# Adafruit_Feather_ESP32-S2_Reverse_TFT.net
KiCad netlist of a schematic drawn in EAGLE
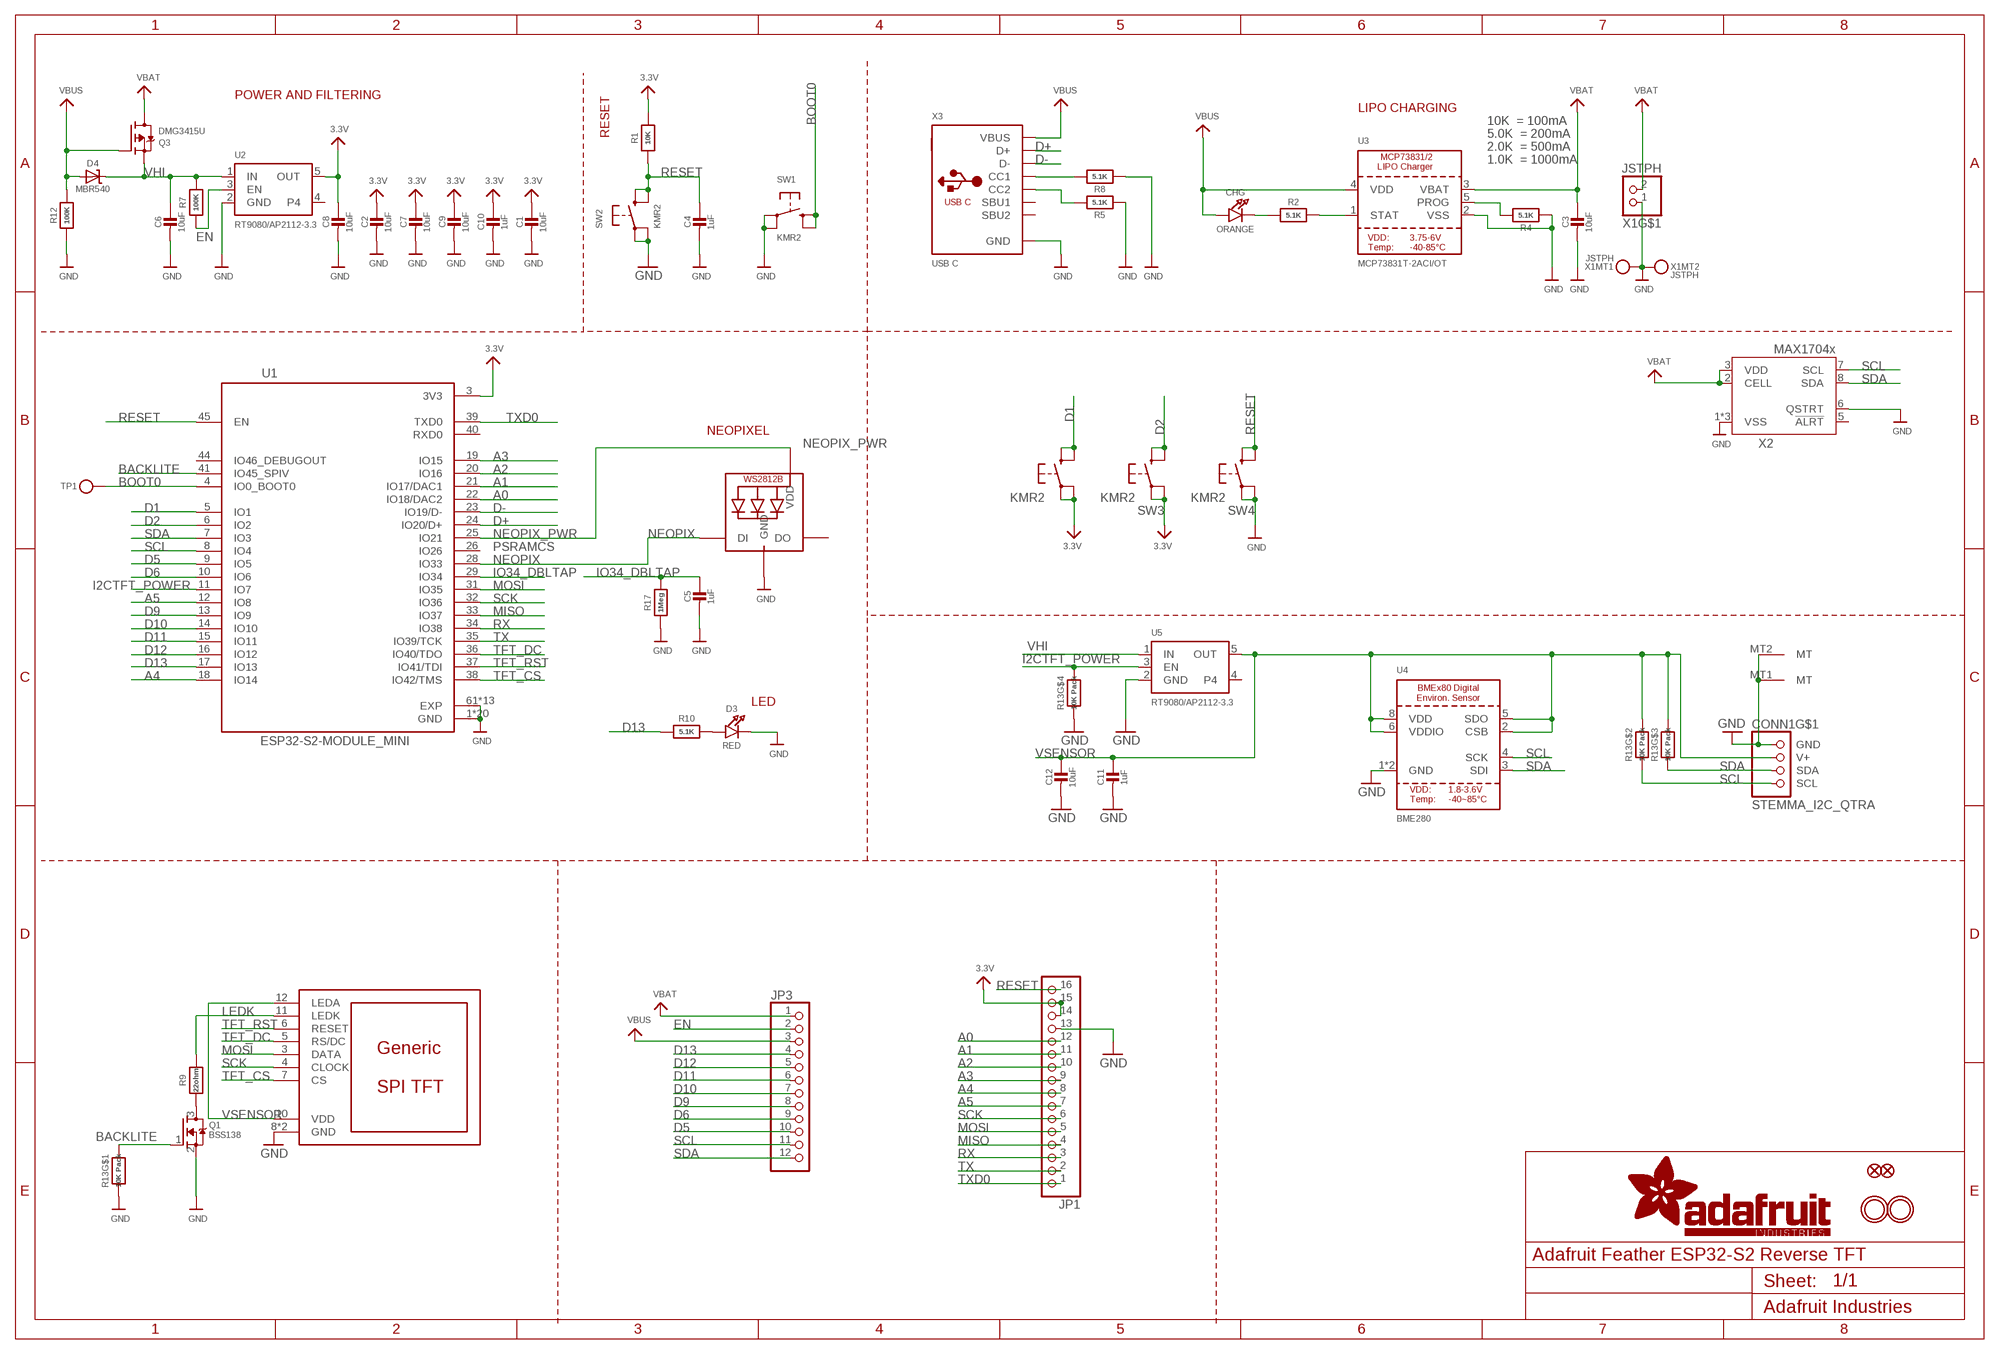
[diagram p0: schematic, sheet 1]

(export (version "E")
  (design (tool "Eeschema 10.0.6"))
  (components
    (comp (ref "C1")
      (value "10uF")
      (footprint "eagle-import:0805-NO")
      (libsource (lib "eagle-import") (part "CAP_CERAMIC0805-NOOUTLINE"))
    )
    (comp (ref "C2")
      (value "10uF")
      (footprint "eagle-import:0805-NO")
      (libsource (lib "eagle-import") (part "CAP_CERAMIC0805-NOOUTLINE"))
    )
    (comp (ref "C3")
      (value "10uF")
      (footprint "eagle-import:0805-NO")
      (libsource (lib "eagle-import") (part "CAP_CERAMIC0805-NOOUTLINE"))
    )
    (comp (ref "C4")
      (value "1uF")
      (footprint "eagle-import:0603-NO")
      (libsource (lib "eagle-import") (part "CAP_CERAMIC0603_NO"))
    )
    (comp (ref "C5")
      (value "1uF")
      (footprint "eagle-import:0603-NO")
      (libsource (lib "eagle-import") (part "CAP_CERAMIC0603_NO"))
    )
    (comp (ref "C6")
      (value "10uF")
      (footprint "eagle-import:0805-NO")
      (libsource (lib "eagle-import") (part "CAP_CERAMIC0805-NOOUTLINE"))
    )
    (comp (ref "C7")
      (value "10uF")
      (footprint "eagle-import:0805-NO")
      (libsource (lib "eagle-import") (part "CAP_CERAMIC0805-NOOUTLINE"))
    )
    (comp (ref "C8")
      (value "10uF")
      (footprint "eagle-import:0805-NO")
      (libsource (lib "eagle-import") (part "CAP_CERAMIC0805-NOOUTLINE"))
    )
    (comp (ref "C9")
      (value "10uF")
      (footprint "eagle-import:0805-NO")
      (libsource (lib "eagle-import") (part "CAP_CERAMIC0805-NOOUTLINE"))
    )
    (comp (ref "C10")
      (value "1uF")
      (footprint "eagle-import:0603-NO")
      (libsource (lib "eagle-import") (part "CAP_CERAMIC0603_NO"))
    )
    (comp (ref "C11")
      (value "1uF")
      (footprint "eagle-import:0603-NO")
      (libsource (lib "eagle-import") (part "CAP_CERAMIC0603_NO"))
    )
    (comp (ref "C12")
      (value "10uF")
      (footprint "eagle-import:0805-NO")
      (libsource (lib "eagle-import") (part "CAP_CERAMIC0805-NOOUTLINE"))
    )
    (comp (ref "CHG")
      (value "ORANGE")
      (footprint "eagle-import:CHIPLED_0603_NOOUTLINE")
      (libsource (lib "eagle-import") (part "LED0603_NOOUTLINE"))
    )
    (comp (ref "CONN1")
      (value "STEMMA_I2C_QTRA")
      (footprint "eagle-import:JST_SH4_RA")
      (libsource (lib "eagle-import") (part "STEMMA_I2C_QTRA"))
    )
    (comp (ref "D3")
      (value "RED")
      (footprint "eagle-import:CHIPLED_0603_NOOUTLINE")
      (libsource (lib "eagle-import") (part "LED0603_NOOUTLINE"))
    )
    (comp (ref "D4")
      (value "MBR540")
      (footprint "eagle-import:SOD-123")
      (libsource (lib "eagle-import") (part "DIODE-SCHOTTKYSOD-123"))
    )
    (comp (ref "DISP1")
      (value "DISP_LCD_GENERIC_SPI_1.14IN_240X135_WRAPUNDER")
      (footprint "eagle-import:TFT_1.14IN_240X135_WRAPUNDER")
      (libsource (lib "eagle-import") (part "DISP_LCD_GENERIC_SPI_1.14IN_240X135_WRAPUNDER"))
    )
    (comp (ref "JP1")
      (value "HEADER-1X16_MIN")
      (footprint "eagle-import:1X16_ROUND_MIN")
      (libsource (lib "eagle-import") (part "HEADER-1X16_MIN"))
    )
    (comp (ref "JP3")
      (value "HEADER-1X12_MIN")
      (footprint "eagle-import:1X12_ROUND_MIN")
      (libsource (lib "eagle-import") (part "HEADER-1X12_MIN"))
    )
    (comp (ref "LED1")
      (value "WS2812B_SK6805_1515")
      (footprint "eagle-import:SK6805_1515")
      (libsource (lib "eagle-import") (part "WS2812B_SK6805_1515"))
    )
    (comp (ref "Q1")
      (value "BSS138")
      (footprint "eagle-import:SC70")
      (libsource (lib "eagle-import") (part "MOSFET-N_SC70"))
    )
    (comp (ref "Q3")
      (value "DMG3415U")
      (footprint "eagle-import:SOT23-R")
      (libsource (lib "eagle-import") (part "MOSFET-P"))
    )
    (comp (ref "R1")
      (value "10K")
      (footprint "eagle-import:0603-NO")
      (libsource (lib "eagle-import") (part "RESISTOR_0603_NOOUT"))
    )
    (comp (ref "R2")
      (value "5.1K")
      (footprint "eagle-import:0603-NO")
      (libsource (lib "eagle-import") (part "RESISTOR_0603_NOOUT"))
    )
    (comp (ref "R4")
      (value "5.1K")
      (footprint "eagle-import:0603-NO")
      (libsource (lib "eagle-import") (part "RESISTOR_0603_NOOUT"))
    )
    (comp (ref "R5")
      (value "5.1K")
      (footprint "eagle-import:0603-NO")
      (libsource (lib "eagle-import") (part "RESISTOR_0603_NOOUT"))
    )
    (comp (ref "R7")
      (value "100K")
      (footprint "eagle-import:0603-NO")
      (libsource (lib "eagle-import") (part "RESISTOR_0603_NOOUT"))
    )
    (comp (ref "R8")
      (value "5.1K")
      (footprint "eagle-import:0603-NO")
      (libsource (lib "eagle-import") (part "RESISTOR_0603_NOOUT"))
    )
    (comp (ref "R9")
      (value "22ohm")
      (footprint "eagle-import:0603-NO")
      (libsource (lib "eagle-import") (part "RESISTOR_0603_NOOUT"))
    )
    (comp (ref "R10")
      (value "5.1K")
      (footprint "eagle-import:0603-NO")
      (libsource (lib "eagle-import") (part "RESISTOR_0603_NOOUT"))
    )
    (comp (ref "R12")
      (value "100K")
      (footprint "eagle-import:0603-NO")
      (libsource (lib "eagle-import") (part "RESISTOR_0603_NOOUT"))
    )
    (comp (ref "R13")
      (value "10K Pack")
      (footprint "eagle-import:RESPACK_4X0603")
      (libsource (lib "eagle-import") (part "RESISTOR_4PACK"))
    )
    (comp (ref "R17")
      (value "1Meg")
      (footprint "eagle-import:0603-NO")
      (libsource (lib "eagle-import") (part "RESISTOR_0603_NOOUT"))
    )
    (comp (ref "SW1")
      (value "KMR2")
      (footprint "eagle-import:BTN_RKB2_4.6X2.8")
      (libsource (lib "eagle-import") (part "SWITCH_TACT_SMT_RKB2"))
    )
    (comp (ref "SW2")
      (value "KMR2")
      (footprint "eagle-import:BTN_RKB2_4.6X2.8")
      (libsource (lib "eagle-import") (part "SWITCH_TACT_SMT_RKB2"))
    )
    (comp (ref "SW3")
      (value "KMR2")
      (footprint "eagle-import:BTN_RKB2_4.6X2.8")
      (libsource (lib "eagle-import") (part "SWITCH_TACT_SMT_RKB2"))
    )
    (comp (ref "SW4")
      (value "KMR2")
      (footprint "eagle-import:BTN_RKB2_4.6X2.8")
      (libsource (lib "eagle-import") (part "SWITCH_TACT_SMT_RKB2"))
    )
    (comp (ref "SW5")
      (value "KMR2")
      (footprint "eagle-import:BTN_RKB2_4.6X2.8")
      (libsource (lib "eagle-import") (part "SWITCH_TACT_SMT_RKB2"))
    )
    (comp (ref "TP1")
      (value "TESTPOINTROUND1.5MMNO")
      (footprint "eagle-import:TESTPOINT_ROUND_1.5MM_NO")
      (libsource (lib "eagle-import") (part "TESTPOINTROUND1.5MMNO"))
    )
    (comp (ref "U$31")
      (value "MOUNTINGHOLE2.5")
      (footprint "eagle-import:MOUNTINGHOLE_2.5_PLATED")
      (libsource (lib "eagle-import") (part "MOUNTINGHOLE2.5"))
    )
    (comp (ref "U$32")
      (value "MOUNTINGHOLE2.5")
      (footprint "eagle-import:MOUNTINGHOLE_2.5_PLATED")
      (libsource (lib "eagle-import") (part "MOUNTINGHOLE2.5"))
    )
    (comp (ref "U$34")
      (value "FIDUCIAL_1MM")
      (footprint "eagle-import:FIDUCIAL_1MM")
      (libsource (lib "eagle-import") (part "FIDUCIAL_1MM"))
    )
    (comp (ref "U$35")
      (value "FIDUCIAL_1MM")
      (footprint "eagle-import:FIDUCIAL_1MM")
      (libsource (lib "eagle-import") (part "FIDUCIAL_1MM"))
    )
    (comp (ref "U1")
      (value "ESP32-S2-MODULE_MINI")
      (footprint "eagle-import:ESP32-S2-MINI-1")
      (libsource (lib "eagle-import") (part "ESP32-S2-MODULE_MINI"))
    )
    (comp (ref "U2")
      (value "RT9080/AP2112-3.3")
      (footprint "eagle-import:SOT23-5")
      (fields (field (name "JLC_ROTATION") "0"))
      (libsource (lib "eagle-import") (part "VREG_SOT23-5"))
    )
    (comp (ref "U3")
      (value "MCP73831T-2ACI/OT")
      (footprint "eagle-import:SOT23-5")
      (libsource (lib "eagle-import") (part "MCP73831/2"))
    )
    (comp (ref "U4")
      (value "BME280")
      (footprint "eagle-import:BME280")
      (libsource (lib "eagle-import") (part "BME280"))
    )
    (comp (ref "U5")
      (value "RT9080/AP2112-3.3")
      (footprint "eagle-import:SOT23-5")
      (fields (field (name "JLC_ROTATION") "0"))
      (libsource (lib "eagle-import") (part "VREG_SOT23-5"))
    )
    (comp (ref "X1")
      (value "JSTPH")
      (footprint "eagle-import:JSTPH2_BATT")
      (libsource (lib "eagle-import") (part "CON_JST_PH_2PIN_MT_BATT"))
    )
    (comp (ref "X2")
      (value "MAX17048/T")
      (footprint "eagle-import:TDFN8_2X2MM")
      (libsource (lib "eagle-import") (part "MAX17048/T"))
    )
    (comp (ref "X3")
      (value "USB C")
      (footprint "eagle-import:USB_C_CUSB31-CFM2AX-01-X")
      (libsource (lib "eagle-import") (part "USB_C"))
    )
  )
  (nets
    (net (code "1") (name "/A0") (class "Default")
      (node (ref "JP1") (pin "12") (pinfunction "12_12") (pintype "passive"))
      (node (ref "U1") (pin "22") (pinfunction "IO18/DAC2_22") (pintype "bidirectional"))
    )
    (net (code "2") (name "/A1") (class "Default")
      (node (ref "JP1") (pin "11") (pinfunction "11_11") (pintype "passive"))
      (node (ref "U1") (pin "21") (pinfunction "IO17/DAC1_21") (pintype "bidirectional"))
    )
    (net (code "3") (name "/A2") (class "Default")
      (node (ref "JP1") (pin "10") (pinfunction "10_10") (pintype "passive"))
      (node (ref "U1") (pin "20") (pinfunction "IO16_20") (pintype "bidirectional"))
    )
    (net (code "4") (name "/A3") (class "Default")
      (node (ref "JP1") (pin "9") (pinfunction "9_9") (pintype "passive"))
      (node (ref "U1") (pin "19") (pinfunction "IO15_19") (pintype "bidirectional"))
    )
    (net (code "5") (name "/A4") (class "Default")
      (node (ref "JP1") (pin "8") (pinfunction "8_8") (pintype "passive"))
      (node (ref "U1") (pin "18") (pinfunction "IO14_18") (pintype "bidirectional"))
    )
    (net (code "6") (name "/A5") (class "Default")
      (node (ref "JP1") (pin "7") (pinfunction "7_7") (pintype "passive"))
      (node (ref "U1") (pin "12") (pinfunction "IO8_12") (pintype "bidirectional"))
    )
    (net (code "7") (name "/BACKLITE") (class "Default")
      (node (ref "Q1") (pin "1") (pinfunction "G_1") (pintype "bidirectional"))
      (node (ref "R13") (pin "8") (pinfunction "2_8") (pintype "passive"))
      (node (ref "U1") (pin "41") (pinfunction "IO45_SPIV_41") (pintype "bidirectional"))
    )
    (net (code "8") (name "/BOOT0") (class "Default")
      (node (ref "SW1") (pin "B") (pinfunction "S_B") (pintype "passive"))
      (node (ref "SW1") (pin "B'") (pinfunction "S1_B'") (pintype "passive"))
      (node (ref "TP1") (pin "P$1") (pinfunction "P$1_P$1") (pintype "bidirectional"))
      (node (ref "U1") (pin "4") (pinfunction "IO0_BOOT0_4") (pintype "bidirectional"))
    )
    (net (code "9") (name "/D+") (class "Default")
      (node (ref "U1") (pin "24") (pinfunction "IO20/D+_24") (pintype "bidirectional"))
      (node (ref "X3") (pin "A6") (pinfunction "D+_A6") (pintype "bidirectional"))
      (node (ref "X3") (pin "B6") (pinfunction "D+_B6") (pintype "bidirectional"))
    )
    (net (code "10") (name "/D-") (class "Default")
      (node (ref "U1") (pin "23") (pinfunction "IO19/D-_23") (pintype "bidirectional"))
      (node (ref "X3") (pin "A7") (pinfunction "D-_A7") (pintype "bidirectional"))
      (node (ref "X3") (pin "B7") (pinfunction "D-_B7") (pintype "bidirectional"))
    )
    (net (code "11") (name "/D1") (class "Default")
      (node (ref "SW5") (pin "B") (pinfunction "S_B") (pintype "passive"))
      (node (ref "SW5") (pin "B'") (pinfunction "S1_B'") (pintype "passive"))
      (node (ref "U1") (pin "5") (pinfunction "IO1_5") (pintype "bidirectional"))
    )
    (net (code "12") (name "/D2") (class "Default")
      (node (ref "SW3") (pin "B") (pinfunction "S_B") (pintype "passive"))
      (node (ref "SW3") (pin "B'") (pinfunction "S1_B'") (pintype "passive"))
      (node (ref "U1") (pin "6") (pinfunction "IO2_6") (pintype "bidirectional"))
    )
    (net (code "13") (name "/D5") (class "Default")
      (node (ref "JP3") (pin "10") (pinfunction "10_10") (pintype "passive"))
      (node (ref "U1") (pin "9") (pinfunction "IO5_9") (pintype "bidirectional"))
    )
    (net (code "14") (name "/D6") (class "Default")
      (node (ref "JP3") (pin "9") (pinfunction "9_9") (pintype "passive"))
      (node (ref "U1") (pin "10") (pinfunction "IO6_10") (pintype "bidirectional"))
    )
    (net (code "15") (name "/D9") (class "Default")
      (node (ref "JP3") (pin "8") (pinfunction "8_8") (pintype "passive"))
      (node (ref "U1") (pin "13") (pinfunction "IO9_13") (pintype "bidirectional"))
    )
    (net (code "16") (name "/D10") (class "Default")
      (node (ref "JP3") (pin "7") (pinfunction "7_7") (pintype "passive"))
      (node (ref "U1") (pin "14") (pinfunction "IO10_14") (pintype "bidirectional"))
    )
    (net (code "17") (name "/D11") (class "Default")
      (node (ref "JP3") (pin "6") (pinfunction "6_6") (pintype "passive"))
      (node (ref "U1") (pin "15") (pinfunction "IO11_15") (pintype "bidirectional"))
    )
    (net (code "18") (name "/D12") (class "Default")
      (node (ref "JP3") (pin "5") (pinfunction "5_5") (pintype "passive"))
      (node (ref "U1") (pin "16") (pinfunction "IO12_16") (pintype "bidirectional"))
    )
    (net (code "19") (name "/D13") (class "Default")
      (node (ref "JP3") (pin "4") (pinfunction "4_4") (pintype "passive"))
      (node (ref "R10") (pin "1") (pinfunction "1_1") (pintype "passive"))
      (node (ref "U1") (pin "17") (pinfunction "IO13_17") (pintype "bidirectional"))
    )
    (net (code "20") (name "/EN") (class "Default")
      (node (ref "JP3") (pin "2") (pinfunction "2_2") (pintype "passive"))
      (node (ref "R7") (pin "1") (pinfunction "1_1") (pintype "passive"))
      (node (ref "U2") (pin "3") (pinfunction "EN_3") (pintype "input"))
    )
    (net (code "21") (name "/I2CTFT_POWER") (class "Default")
      (node (ref "R13") (pin "5") (pinfunction "2_5") (pintype "passive"))
      (node (ref "U1") (pin "11") (pinfunction "IO7_11") (pintype "bidirectional"))
      (node (ref "U5") (pin "3") (pinfunction "EN_3") (pintype "input"))
    )
    (net (code "22") (name "/IO34_DBLTAP") (class "Default")
      (node (ref "C5") (pin "1") (pinfunction "1_1") (pintype "passive"))
      (node (ref "R17") (pin "2") (pinfunction "2_2") (pintype "passive"))
      (node (ref "U1") (pin "29") (pinfunction "IO34_29") (pintype "input"))
    )
    (net (code "23") (name "/LEDK") (class "Default")
      (node (ref "DISP1") (pin "11") (pinfunction "LEDK_11") (pintype "input"))
      (node (ref "R9") (pin "2") (pinfunction "2_2") (pintype "passive"))
    )
    (net (code "24") (name "/MISO") (class "Default")
      (node (ref "JP1") (pin "4") (pinfunction "4_4") (pintype "passive"))
      (node (ref "U1") (pin "33") (pinfunction "IO37_33") (pintype "bidirectional"))
    )
    (net (code "25") (name "/MOSI") (class "Default")
      (node (ref "DISP1") (pin "3") (pinfunction "DATA_3") (pintype "bidirectional"))
      (node (ref "JP1") (pin "5") (pinfunction "5_5") (pintype "passive"))
      (node (ref "U1") (pin "31") (pinfunction "IO35_31") (pintype "input"))
    )
    (net (code "26") (name "/NEOPIX") (class "Default")
      (node (ref "LED1") (pin "1") (pinfunction "DI_1") (pintype "input"))
      (node (ref "U1") (pin "28") (pinfunction "IO33_28") (pintype "bidirectional"))
    )
    (net (code "27") (name "/NEOPIX_PWR") (class "Default")
      (node (ref "LED1") (pin "2") (pinfunction "VDD_2") (pintype "power_in"))
      (node (ref "U1") (pin "25") (pinfunction "IO21_25") (pintype "bidirectional"))
    )
    (net (code "28") (name "/RESET") (class "Default")
      (node (ref "C4") (pin "1") (pinfunction "1_1") (pintype "passive"))
      (node (ref "JP1") (pin "16") (pinfunction "16_16") (pintype "passive"))
      (node (ref "R1") (pin "1") (pinfunction "1_1") (pintype "passive"))
      (node (ref "SW2") (pin "B") (pinfunction "S_B") (pintype "passive"))
      (node (ref "SW2") (pin "B'") (pinfunction "S1_B'") (pintype "passive"))
      (node (ref "SW4") (pin "B") (pinfunction "S_B") (pintype "passive"))
      (node (ref "SW4") (pin "B'") (pinfunction "S1_B'") (pintype "passive"))
      (node (ref "U1") (pin "45") (pinfunction "EN_45") (pintype "input"))
    )
    (net (code "29") (name "/RX") (class "Default")
      (node (ref "JP1") (pin "3") (pinfunction "3_3") (pintype "passive"))
      (node (ref "U1") (pin "34") (pinfunction "IO38_34") (pintype "bidirectional"))
    )
    (net (code "30") (name "/SCK") (class "Default")
      (node (ref "DISP1") (pin "4") (pinfunction "CLOCK_4") (pintype "input"))
      (node (ref "JP1") (pin "6") (pinfunction "6_6") (pintype "passive"))
      (node (ref "U1") (pin "32") (pinfunction "IO36_32") (pintype "bidirectional"))
    )
    (net (code "31") (name "/SCL") (class "Default")
      (node (ref "CONN1") (pin "4") (pinfunction "SCL_4") (pintype "passive"))
      (node (ref "JP3") (pin "11") (pinfunction "11_11") (pintype "passive"))
      (node (ref "R13") (pin "2") (pinfunction "1_2") (pintype "passive"))
      (node (ref "U1") (pin "8") (pinfunction "IO4_8") (pintype "bidirectional"))
      (node (ref "U4") (pin "4") (pinfunction "SCK_4") (pintype "input"))
      (node (ref "X2") (pin "7") (pinfunction "SCL_7") (pintype "bidirectional"))
    )
    (net (code "32") (name "/SDA") (class "Default")
      (node (ref "CONN1") (pin "3") (pinfunction "SDA_3") (pintype "passive"))
      (node (ref "JP3") (pin "12") (pinfunction "12_12") (pintype "passive"))
      (node (ref "R13") (pin "3") (pinfunction "1_3") (pintype "passive"))
      (node (ref "U1") (pin "7") (pinfunction "IO3_7") (pintype "bidirectional"))
      (node (ref "U4") (pin "3") (pinfunction "SDI_3") (pintype "input"))
      (node (ref "X2") (pin "8") (pinfunction "SDA_8") (pintype "bidirectional"))
    )
    (net (code "33") (name "/TFT_CS") (class "Default")
      (node (ref "DISP1") (pin "7") (pinfunction "CS_7") (pintype "input"))
      (node (ref "U1") (pin "38") (pinfunction "IO42/TMS_38") (pintype "bidirectional"))
    )
    (net (code "34") (name "/TFT_DC") (class "Default")
      (node (ref "DISP1") (pin "5") (pinfunction "RS/DC_5") (pintype "input"))
      (node (ref "U1") (pin "36") (pinfunction "IO40/TDO_36") (pintype "bidirectional"))
    )
    (net (code "35") (name "/TFT_RST") (class "Default")
      (node (ref "DISP1") (pin "6") (pinfunction "RESET_6") (pintype "input"))
      (node (ref "U1") (pin "37") (pinfunction "IO41/TDI_37") (pintype "bidirectional"))
    )
    (net (code "36") (name "/TX") (class "Default")
      (node (ref "JP1") (pin "2") (pinfunction "2_2") (pintype "passive"))
      (node (ref "U1") (pin "35") (pinfunction "IO39/TCK_35") (pintype "bidirectional"))
    )
    (net (code "37") (name "/TXD0") (class "Default")
      (node (ref "JP1") (pin "1") (pinfunction "1_1") (pintype "passive"))
      (node (ref "U1") (pin "39") (pinfunction "TXD0_39") (pintype "bidirectional"))
    )
    (net (code "38") (name "/VHI") (class "Default")
      (node (ref "C6") (pin "1") (pinfunction "1_1") (pintype "passive"))
      (node (ref "D4") (pin "C") (pinfunction "C_C") (pintype "passive"))
      (node (ref "Q3") (pin "2") (pinfunction "S_2") (pintype "passive"))
      (node (ref "R7") (pin "2") (pinfunction "2_2") (pintype "passive"))
      (node (ref "U2") (pin "1") (pinfunction "IN_1") (pintype "power_in"))
      (node (ref "U5") (pin "1") (pinfunction "IN_1") (pintype "power_in"))
    )
    (net (code "39") (name "/VSENSOR") (class "Default")
      (node (ref "C11") (pin "1") (pinfunction "1_1") (pintype "passive"))
      (node (ref "C12") (pin "1") (pinfunction "1_1") (pintype "passive"))
      (node (ref "CONN1") (pin "2") (pinfunction "V+_2") (pintype "passive"))
      (node (ref "DISP1") (pin "10") (pinfunction "VDD_10") (pintype "power_in"))
      (node (ref "DISP1") (pin "12") (pinfunction "LEDA_12") (pintype "input"))
      (node (ref "R13") (pin "6") (pinfunction "2_6") (pintype "passive"))
      (node (ref "R13") (pin "7") (pinfunction "2_7") (pintype "passive"))
      (node (ref "U4") (pin "2") (pinfunction "CSB_2") (pintype "input"))
      (node (ref "U4") (pin "5") (pinfunction "SDO_5") (pintype "output"))
      (node (ref "U4") (pin "6") (pinfunction "VDDIO_6") (pintype "power_in"))
      (node (ref "U4") (pin "8") (pinfunction "VDD_8") (pintype "power_in"))
      (node (ref "U5") (pin "5") (pinfunction "OUT_5") (pintype "power_in"))
    )
    (net (code "40") (name "3.3V") (class "Default")
      (node (ref "C1") (pin "1") (pinfunction "1_1") (pintype "passive"))
      (node (ref "C10") (pin "1") (pinfunction "1_1") (pintype "passive"))
      (node (ref "C2") (pin "1") (pinfunction "1_1") (pintype "passive"))
      (node (ref "C7") (pin "1") (pinfunction "1_1") (pintype "passive"))
      (node (ref "C8") (pin "1") (pinfunction "1_1") (pintype "passive"))
      (node (ref "C9") (pin "1") (pinfunction "1_1") (pintype "passive"))
      (node (ref "JP1") (pin "14") (pinfunction "14_14") (pintype "passive"))
      (node (ref "JP1") (pin "15") (pinfunction "15_15") (pintype "passive"))
      (node (ref "R1") (pin "2") (pinfunction "2_2") (pintype "passive"))
      (node (ref "SW3") (pin "A") (pinfunction "P_A") (pintype "passive"))
      (node (ref "SW3") (pin "A'") (pinfunction "P1_A'") (pintype "passive"))
      (node (ref "SW5") (pin "A") (pinfunction "P_A") (pintype "passive"))
      (node (ref "SW5") (pin "A'") (pinfunction "P1_A'") (pintype "passive"))
      (node (ref "U1") (pin "3") (pinfunction "3V3_3") (pintype "power_in"))
      (node (ref "U2") (pin "5") (pinfunction "OUT_5") (pintype "power_in"))
    )
    (net (code "41") (name "GND") (class "Default")
      (node (ref "C1") (pin "2") (pinfunction "2_2") (pintype "passive"))
      (node (ref "C10") (pin "2") (pinfunction "2_2") (pintype "passive"))
      (node (ref "C11") (pin "2") (pinfunction "2_2") (pintype "passive"))
      (node (ref "C12") (pin "2") (pinfunction "2_2") (pintype "passive"))
      (node (ref "C2") (pin "2") (pinfunction "2_2") (pintype "passive"))
      (node (ref "C3") (pin "2") (pinfunction "2_2") (pintype "passive"))
      (node (ref "C4") (pin "2") (pinfunction "2_2") (pintype "passive"))
      (node (ref "C5") (pin "2") (pinfunction "2_2") (pintype "passive"))
      (node (ref "C6") (pin "2") (pinfunction "2_2") (pintype "passive"))
      (node (ref "C7") (pin "2") (pinfunction "2_2") (pintype "passive"))
      (node (ref "C8") (pin "2") (pinfunction "2_2") (pintype "passive"))
      (node (ref "C9") (pin "2") (pinfunction "2_2") (pintype "passive"))
      (node (ref "CONN1") (pin "1") (pinfunction "GND_1") (pintype "passive"))
      (node (ref "CONN1") (pin "MT1") (pinfunction "MT_MT1") (pintype "bidirectional"))
      (node (ref "CONN1") (pin "MT2") (pinfunction "MT_MT2") (pintype "bidirectional"))
      (node (ref "D3") (pin "C") (pinfunction "C_C") (pintype "passive"))
      (node (ref "DISP1") (pin "13") (pinfunction "GND_13") (pintype "power_in"))
      (node (ref "DISP1") (pin "8") (pinfunction "GND_8") (pintype "power_in"))
      (node (ref "JP1") (pin "13") (pinfunction "13_13") (pintype "passive"))
      (node (ref "LED1") (pin "4") (pinfunction "GND_4") (pintype "power_in"))
      (node (ref "Q1") (pin "2") (pinfunction "S_2") (pintype "bidirectional"))
      (node (ref "R12") (pin "1") (pinfunction "1_1") (pintype "passive"))
      (node (ref "R13") (pin "1") (pinfunction "1_1") (pintype "passive"))
      (node (ref "R13") (pin "4") (pinfunction "1_4") (pintype "passive"))
      (node (ref "R17") (pin "1") (pinfunction "1_1") (pintype "passive"))
      (node (ref "R4") (pin "1") (pinfunction "1_1") (pintype "passive"))
      (node (ref "R5") (pin "1") (pinfunction "1_1") (pintype "passive"))
      (node (ref "R8") (pin "1") (pinfunction "1_1") (pintype "passive"))
      (node (ref "SW1") (pin "A") (pinfunction "P_A") (pintype "passive"))
      (node (ref "SW1") (pin "A'") (pinfunction "P1_A'") (pintype "passive"))
      (node (ref "SW2") (pin "A") (pinfunction "P_A") (pintype "passive"))
      (node (ref "SW2") (pin "A'") (pinfunction "P1_A'") (pintype "passive"))
      (node (ref "SW4") (pin "A") (pinfunction "P_A") (pintype "passive"))
      (node (ref "SW4") (pin "A'") (pinfunction "P1_A'") (pintype "passive"))
      (node (ref "U1") (pin "1") (pinfunction "GND_1") (pintype "power_in"))
      (node (ref "U1") (pin "2") (pinfunction "GND_2") (pintype "power_in"))
      (node (ref "U1") (pin "30") (pinfunction "GND_30") (pintype "power_in"))
      (node (ref "U1") (pin "42") (pinfunction "GND_42") (pintype "power_in"))
      (node (ref "U1") (pin "43") (pinfunction "GND_43") (pintype "power_in"))
      (node (ref "U1") (pin "46") (pinfunction "GND_46") (pintype "power_in"))
      (node (ref "U1") (pin "47") (pinfunction "GND_47") (pintype "power_in"))
      (node (ref "U1") (pin "48") (pinfunction "GND_48") (pintype "power_in"))
      (node (ref "U1") (pin "49") (pinfunction "GND_49") (pintype "power_in"))
      (node (ref "U1") (pin "50") (pinfunction "GND_50") (pintype "power_in"))
      (node (ref "U1") (pin "51") (pinfunction "GND_51") (pintype "power_in"))
      (node (ref "U1") (pin "52") (pinfunction "GND_52") (pintype "power_in"))
      (node (ref "U1") (pin "53") (pinfunction "GND_53") (pintype "power_in"))
      (node (ref "U1") (pin "54") (pinfunction "GND_54") (pintype "power_in"))
      (node (ref "U1") (pin "55") (pinfunction "GND_55") (pintype "power_in"))
      (node (ref "U1") (pin "56") (pinfunction "GND_56") (pintype "power_in"))
      (node (ref "U1") (pin "57") (pinfunction "GND_57") (pintype "power_in"))
      (node (ref "U1") (pin "58") (pinfunction "GND_58") (pintype "power_in"))
      (node (ref "U1") (pin "59") (pinfunction "GND_59") (pintype "power_in"))
      (node (ref "U1") (pin "60") (pinfunction "GND_60") (pintype "power_in"))
      (node (ref "U1") (pin "61") (pinfunction "EXP_61") (pintype "power_in"))
      (node (ref "U1") (pin "62") (pinfunction "EXP_62") (pintype "power_in"))
      (node (ref "U1") (pin "63") (pinfunction "EXP_63") (pintype "power_in"))
      (node (ref "U1") (pin "64") (pinfunction "EXP_64") (pintype "power_in"))
      (node (ref "U1") (pin "65") (pinfunction "EXP_65") (pintype "power_in"))
      (node (ref "U1") (pin "66") (pinfunction "EXP_66") (pintype "power_in"))
      (node (ref "U1") (pin "67") (pinfunction "EXP_67") (pintype "power_in"))
      (node (ref "U1") (pin "68") (pinfunction "EXP_68") (pintype "power_in"))
      (node (ref "U1") (pin "69") (pinfunction "EXP_69") (pintype "power_in"))
      (node (ref "U1") (pin "70") (pinfunction "EXP_70") (pintype "power_in"))
      (node (ref "U1") (pin "71") (pinfunction "EXP_71") (pintype "power_in"))
      (node (ref "U1") (pin "72") (pinfunction "EXP_72") (pintype "power_in"))
      (node (ref "U1") (pin "73") (pinfunction "EXP_73") (pintype "power_in"))
      (node (ref "U2") (pin "2") (pinfunction "GND_2") (pintype "power_in"))
      (node (ref "U3") (pin "2") (pinfunction "VSS_2") (pintype "power_in"))
      (node (ref "U4") (pin "1") (pinfunction "GND_1") (pintype "power_in"))
      (node (ref "U4") (pin "7") (pinfunction "GND_7") (pintype "power_in"))
      (node (ref "U5") (pin "2") (pinfunction "GND_2") (pintype "power_in"))
      (node (ref "X1") (pin "1") (pinfunction "1_1") (pintype "passive"))
      (node (ref "X1") (pin "NC1") (pinfunction "P$1_NC1") (pintype "bidirectional"))
      (node (ref "X1") (pin "NC2") (pinfunction "P$1_NC2") (pintype "bidirectional"))
      (node (ref "X2") (pin "1") (pinfunction "VSS_1") (pintype "power_in"))
      (node (ref "X2") (pin "4") (pinfunction "VSS_4") (pintype "power_in"))
      (node (ref "X2") (pin "6") (pinfunction "QSTRT_6") (pintype "input"))
      (node (ref "X2") (pin "THERMAL") (pinfunction "VSS_THERMAL") (pintype "power_in"))
      (node (ref "X3") (pin "A1B12") (pinfunction "GND_A1B12") (pintype "power_in"))
      (node (ref "X3") (pin "B1A12") (pinfunction "GND_B1A12") (pintype "power_in"))
    )
    (net (code "42") (name "Net-(CHG-PadC)") (class "Default")
      (node (ref "CHG") (pin "C") (pinfunction "C_C") (pintype "passive"))
      (node (ref "R2") (pin "1") (pinfunction "1_1") (pintype "passive"))
    )
    (net (code "43") (name "Net-(D3-PadA)") (class "Default")
      (node (ref "D3") (pin "A") (pinfunction "A_A") (pintype "passive"))
      (node (ref "R10") (pin "2") (pinfunction "2_2") (pintype "passive"))
    )
    (net (code "44") (name "Net-(Q1-D)") (class "Default")
      (node (ref "Q1") (pin "3") (pinfunction "D_3") (pintype "bidirectional"))
      (node (ref "R9") (pin "1") (pinfunction "1_1") (pintype "passive"))
    )
    (net (code "45") (name "Net-(U3-PROG)") (class "Default")
      (node (ref "R4") (pin "2") (pinfunction "2_2") (pintype "passive"))
      (node (ref "U3") (pin "5") (pinfunction "PROG_5") (pintype "input"))
    )
    (net (code "46") (name "Net-(U3-STAT)") (class "Default")
      (node (ref "R2") (pin "2") (pinfunction "2_2") (pintype "passive"))
      (node (ref "U3") (pin "1") (pinfunction "STAT_1") (pintype "output"))
    )
    (net (code "47") (name "Net-(X3-CC1)") (class "Default")
      (node (ref "R8") (pin "2") (pinfunction "2_2") (pintype "passive"))
      (node (ref "X3") (pin "A5") (pinfunction "CC1_A5") (pintype "bidirectional"))
    )
    (net (code "48") (name "Net-(X3-CC2)") (class "Default")
      (node (ref "R5") (pin "2") (pinfunction "2_2") (pintype "passive"))
      (node (ref "X3") (pin "B5") (pinfunction "CC2_B5") (pintype "bidirectional"))
    )
    (net (code "49") (name "VBAT") (class "Default")
      (node (ref "C3") (pin "1") (pinfunction "1_1") (pintype "passive"))
      (node (ref "JP3") (pin "1") (pinfunction "1_1") (pintype "passive"))
      (node (ref "Q3") (pin "3") (pinfunction "D_3") (pintype "passive"))
      (node (ref "U3") (pin "3") (pinfunction "VBAT_3") (pintype "power_in"))
      (node (ref "X1") (pin "2") (pinfunction "2_2") (pintype "passive"))
      (node (ref "X2") (pin "2") (pinfunction "CELL_2") (pintype "power_in"))
      (node (ref "X2") (pin "3") (pinfunction "VDD_3") (pintype "power_in"))
    )
    (net (code "50") (name "VBUS") (class "Default")
      (node (ref "CHG") (pin "A") (pinfunction "A_A") (pintype "passive"))
      (node (ref "D4") (pin "A") (pinfunction "A_A") (pintype "passive"))
      (node (ref "JP3") (pin "3") (pinfunction "3_3") (pintype "passive"))
      (node (ref "Q3") (pin "1") (pinfunction "G_1") (pintype "passive"))
      (node (ref "R12") (pin "2") (pinfunction "2_2") (pintype "passive"))
      (node (ref "U3") (pin "4") (pinfunction "VDD_4") (pintype "power_in"))
      (node (ref "X3") (pin "A4B9") (pinfunction "VBUS_A4B9") (pintype "power_in"))
      (node (ref "X3") (pin "B4A9") (pinfunction "VBUS_B4A9") (pintype "power_in"))
    )
    (net (code "51") (name "unconnected-(LED1-DO-Pad3)") (class "Default")
      (node (ref "LED1") (pin "3") (pinfunction "DO_3") (pintype "output"))
    )
    (net (code "52") (name "unconnected-(U1-IO26-Pad26)") (class "Default")
      (node (ref "U1") (pin "26") (pinfunction "IO26_26") (pintype "bidirectional"))
    )
    (net (code "53") (name "unconnected-(U1-IO46_DEBUGOUT-Pad44)") (class "Default")
      (node (ref "U1") (pin "44") (pinfunction "IO46_DEBUGOUT_44") (pintype "input"))
    )
    (net (code "54") (name "unconnected-(U1-RXD0-Pad40)") (class "Default")
      (node (ref "U1") (pin "40") (pinfunction "RXD0_40") (pintype "bidirectional"))
    )
    (net (code "55") (name "unconnected-(U2-P4-Pad4)") (class "Default")
      (node (ref "U2") (pin "4") (pinfunction "P4_4") (pintype "bidirectional"))
    )
    (net (code "56") (name "unconnected-(U5-P4-Pad4)") (class "Default")
      (node (ref "U5") (pin "4") (pinfunction "P4_4") (pintype "bidirectional"))
    )
    (net (code "57") (name "unconnected-(X2-~{ALRT}-Pad5)") (class "Default")
      (node (ref "X2") (pin "5") (pinfunction "~{ALRT}_5") (pintype "output"))
    )
    (net (code "58") (name "unconnected-(X3-SBU1-PadA8)") (class "Default")
      (node (ref "X3") (pin "A8") (pinfunction "SBU1_A8") (pintype "bidirectional"))
    )
    (net (code "59") (name "unconnected-(X3-SBU2-PadB8)") (class "Default")
      (node (ref "X3") (pin "B8") (pinfunction "SBU2_B8") (pintype "bidirectional"))
    )
  )
)
